# PWM.net
KiCad netlist of a schematic drawn in Altium Designer
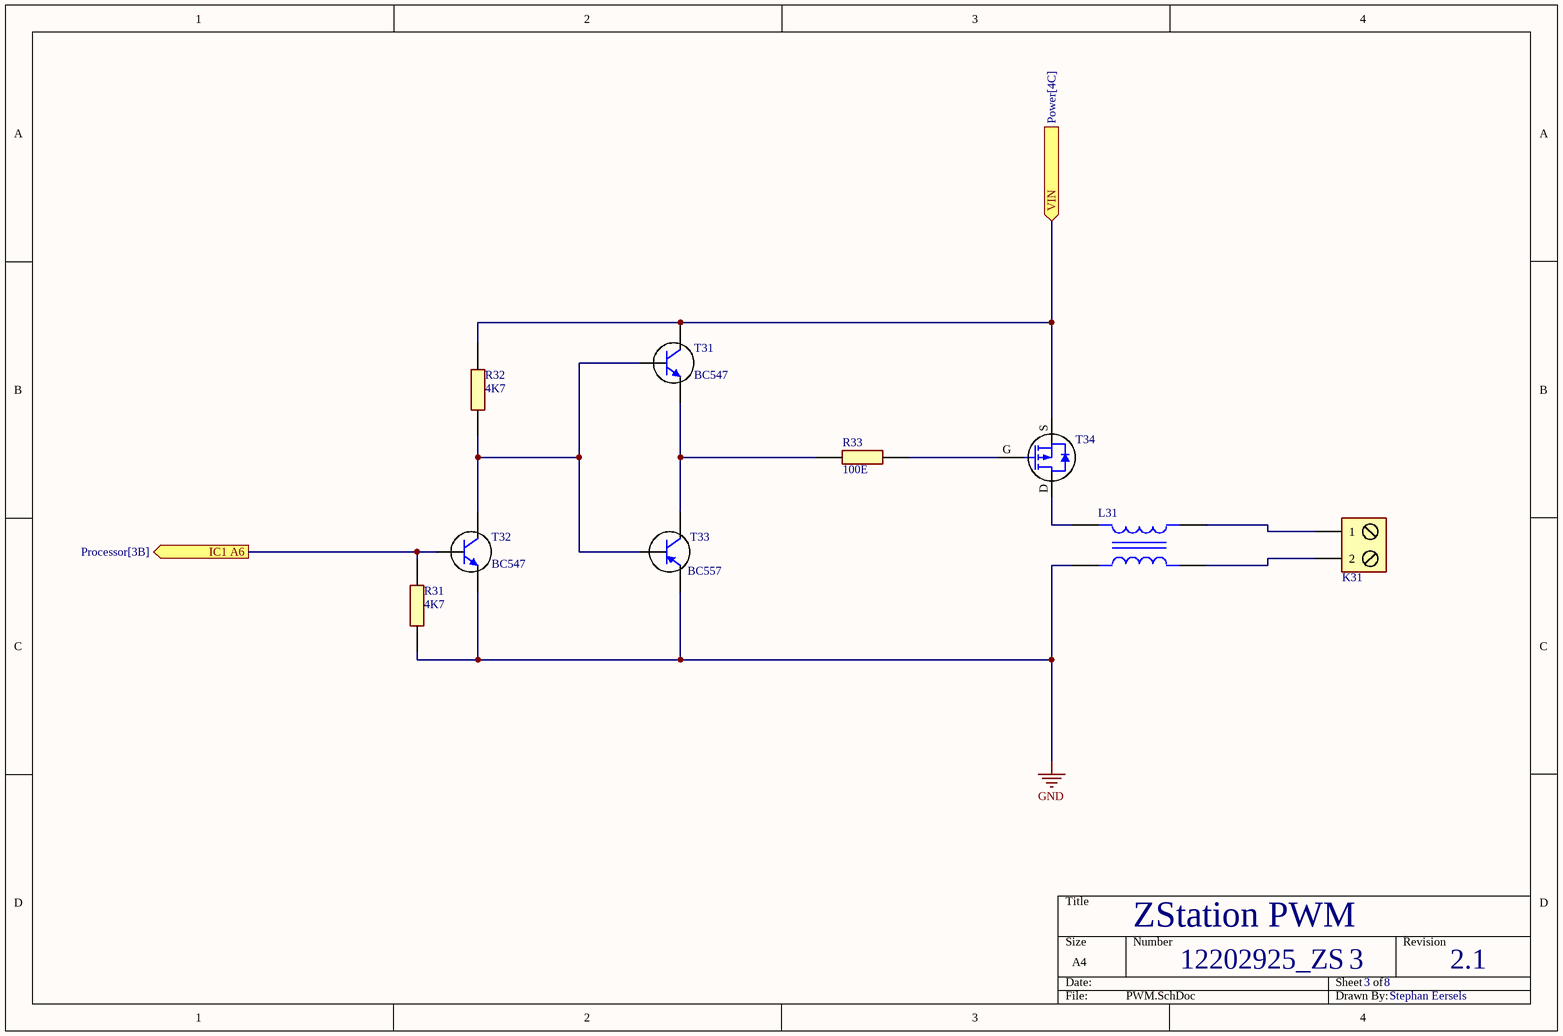
[diagram p0: PWM.SchDoc]

(export (version "E")
  (design (tool "Eeschema 10.0.6"))
  (components
    (comp (ref "K31")
      (value "TBLOCK_2P")
      (footprint "TBLOCK_2P")
      (description "Connector")
      (fields
        (field (name "MANUFACTURER_PART_NUMBER") "691104700002")
        (field (name "MOUSER PART NUMBER") "710-691104700002")
      )
      (libsource (lib "Master") (part "TBLOCK_2P"))
    )
    (comp (ref "L31")
      (value "Common_Mode_Choke")
      (footprint "2545")
      (libsource (lib "Master") (part "Common_Mode_Choke"))
    )
    (comp (ref "R31")
      (value "4K7")
      (footprint "VISHAY_CMF_60")
      (description "Through Hole 1W 10/68 Kohms 1%")
      (fields
        (field (name "MANUFACTURER_PART_NUMBER") "CMF6010K000FKEB")
        (field (name "MOUSER PART NUMBER") "71-CMF6010K000FKEB")
      )
      (libsource (lib "Master") (part "RES_68K_10K"))
    )
    (comp (ref "R32")
      (value "4K7")
      (footprint "VISHAY_CMF_60")
      (description "Through Hole 1W 10/68 Kohms 1%")
      (fields
        (field (name "MANUFACTURER_PART_NUMBER") "CMF6010K000FKEB")
        (field (name "MOUSER PART NUMBER") "71-CMF6010K000FKEB")
      )
      (libsource (lib "Master") (part "RES_68K_10K"))
    )
    (comp (ref "R33")
      (value "100E")
      (footprint "VISHAY_CMF_60")
      (description "Through Hole 1W 10/68 Kohms 1%")
      (fields
        (field (name "MANUFACTURER_PART_NUMBER") "CMF6010K000FKEB")
        (field (name "MOUSER PART NUMBER") "71-CMF6010K000FKEB")
      )
      (libsource (lib "") (part "RES_68K_10K_1"))
    )
    (comp (ref "T31")
      (value "BC547")
      (footprint "ONSC-TO-92-3-29-11")
      (fields (field (name "MANUFACTURER") "On Semiconductor") (field (name "PARTNUMBER") "BC547C"))
      (libsource (lib "Master") (part "Transistor_NPN"))
    )
    (comp (ref "T32")
      (value "BC547")
      (footprint "ONSC-TO-92-3-29-11")
      (fields (field (name "MANUFACTURER") "On Semiconductor") (field (name "PARTNUMBER") "BC547C"))
      (libsource (lib "Master") (part "Transistor_NPN"))
    )
    (comp (ref "T33")
      (value "BC557")
      (footprint "ONSC-TO-92-3-29-11")
      (fields (field (name "MANUFACTURER") "On Semiconductor") (field (name "PARTNUMBER") "BC557C"))
      (libsource (lib "Master") (part "Transistor_PNP"))
    )
    (comp (ref "T34")
      (value "IRF9Z34NPBF")
      (footprint "IRF9Z34NPBF")
      (fields (field (name "MANUFACTURER") "Fairchild Semiconductor"))
      (libsource (lib "Master") (part "MOSFET_P"))
    )
  )
  (nets
    (net (code "1") (name "/IC1 A6") (class "Default")
      (node (ref "R31") (pin "2") (pinfunction "2_2") (pintype "passive"))
      (node (ref "T32") (pin "2") (pinfunction "B_2") (pintype "passive"))
    )
    (net (code "2") (name "/VIN") (class "Default")
      (node (ref "R32") (pin "2") (pinfunction "2_2") (pintype "passive"))
      (node (ref "T31") (pin "1") (pinfunction "C_1") (pintype "passive"))
      (node (ref "T34") (pin "S") (pinfunction "SOURCE_S") (pintype "passive"))
    )
    (net (code "3") (name "GND") (class "Default")
      (node (ref "L31") (pin "2") (pinfunction "2_2") (pintype "passive"))
      (node (ref "R31") (pin "1") (pinfunction "1_1") (pintype "passive"))
      (node (ref "T32") (pin "3") (pinfunction "E_3") (pintype "passive"))
      (node (ref "T33") (pin "3") (pinfunction "E_3") (pintype "passive"))
    )
    (net (code "4") (name "Net-(K31-Pad1)") (class "Default")
      (node (ref "K31") (pin "1") (pinfunction "1_1") (pintype "passive"))
      (node (ref "L31") (pin "4") (pinfunction "4_4") (pintype "passive"))
    )
    (net (code "5") (name "Net-(K31-Pad2)") (class "Default")
      (node (ref "K31") (pin "2") (pinfunction "2_2") (pintype "passive"))
      (node (ref "L31") (pin "3") (pinfunction "3_3") (pintype "passive"))
    )
    (net (code "6") (name "Net-(T31-B)") (class "Default")
      (node (ref "R32") (pin "1") (pinfunction "1_1") (pintype "passive"))
      (node (ref "T31") (pin "2") (pinfunction "B_2") (pintype "passive"))
      (node (ref "T32") (pin "1") (pinfunction "C_1") (pintype "passive"))
      (node (ref "T33") (pin "2") (pinfunction "B_2") (pintype "passive"))
    )
    (net (code "7") (name "Net-(T31-E)") (class "Default")
      (node (ref "R33") (pin "2") (pinfunction "2_2") (pintype "passive"))
      (node (ref "T31") (pin "3") (pinfunction "E_3") (pintype "passive"))
      (node (ref "T33") (pin "1") (pinfunction "C_1") (pintype "passive"))
    )
    (net (code "8") (name "Net-(T34-DRAIN)") (class "Default")
      (node (ref "L31") (pin "1") (pinfunction "1_1") (pintype "passive"))
      (node (ref "T34") (pin "D") (pinfunction "DRAIN_D") (pintype "passive"))
    )
    (net (code "9") (name "Net-(T34-GATE)") (class "Default")
      (node (ref "R33") (pin "1") (pinfunction "1_1") (pintype "passive"))
      (node (ref "T34") (pin "G") (pinfunction "GATE_G") (pintype "passive"))
    )
  )
)
